# EStop.net
KiCad netlist of a schematic drawn in Altium Designer
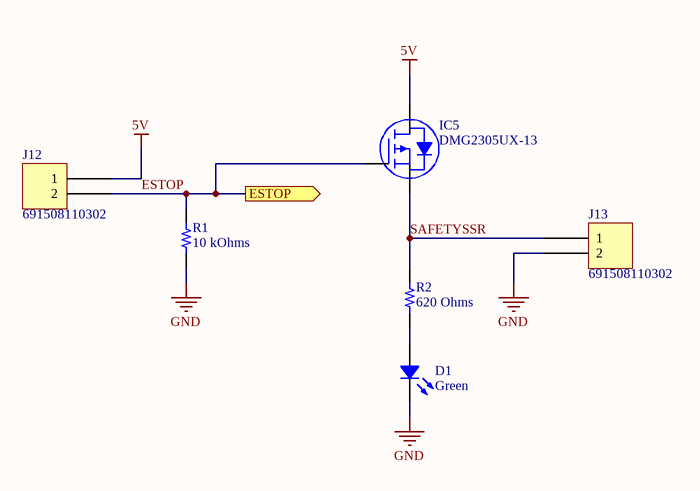
[diagram p0: EStop.SchDoc]

(export (version "E")
  (design (tool "Eeschema 10.0.6"))
  (components
    (comp (ref "D1")
      (value "Green")
      (footprint "LED 0603_1608 GREEN")
      (description "LED GREEN CLEAR CHIP SMD")
      (fields (field (name "PART NUMBER") "LTST-C190KGKT") (field (name "MANUFACTURER") "Lite-On Inc."))
      (libsource (lib "Celestial Altium Library - altium_library") (part "LED"))
    )
    (comp (ref "IC5")
      (value "DMG2305UX-13")
      (footprint "DIODES SOT-23-3")
      (description "MOSFET P-CH 20V 4.2A SOT23")
      (fields (field (name "MANUFACTURER") "Diodes Incorporated"))
      (libsource (lib "Celestial Altium Library - altium_library") (part "DIODES MOSFET P-CH SOT-23-3"))
    )
    (comp (ref "J12")
      (value "691508110302")
      (footprint "WURTH 691508110302")
      (description "TERM BLOCK 2POS 3.5MM SMD")
      (fields (field (name "MANUFACTURER") "Würth Elektronik") (field (name "VOLTAGE") "300V"))
      (libsource (lib "Celestial Altium Library - altium_library") (part "2 Pin"))
    )
    (comp (ref "J13")
      (value "691508110302")
      (footprint "WURTH 691508110302")
      (description "TERM BLOCK 2POS 3.5MM SMD")
      (fields (field (name "MANUFACTURER") "Würth Elektronik") (field (name "VOLTAGE") "300V"))
      (libsource (lib "") (part "2 Pin_1"))
    )
    (comp (ref "R1")
      (value "10 kOhms")
      (footprint "RES 0603_1608")
      (description "RES SMD 10K OHM 5% 1/4W 0603")
      (fields
        (field (name "PART NUMBER") "ERJ-PA3J103V")
        (field (name "MANUFACTURER") "Panasonic Electronic Components")
      )
      (libsource (lib "Celestial Altium Library - altium_library") (part "Resistor"))
    )
    (comp (ref "R2")
      (value "620 Ohms")
      (footprint "RES 0603_1608")
      (description "RES SMD 620 OHM 5% 1/10W 0603")
      (fields
        (field (name "PART NUMBER") "ERJ-3GEYJ621V")
        (field (name "MANUFACTURER") "Panasonic Electronic Components")
      )
      (libsource (lib "Celestial Altium Library - altium_library") (part "Resistor"))
    )
  )
  (nets
    (net (code "1") (name "/ESTOP") (class "Default")
      (node (ref "IC5") (pin "1") (pinfunction "G_1") (pintype "passive"))
      (node (ref "J12") (pin "2") (pinfunction "2_2") (pintype "passive"))
      (node (ref "R1") (pin "2") (pinfunction "2_2") (pintype "passive"))
    )
    (net (code "2") (name "/SAFETYSSR") (class "Default")
      (node (ref "IC5") (pin "2") (pinfunction "S_2") (pintype "passive"))
      (node (ref "J13") (pin "1") (pinfunction "1_1") (pintype "passive"))
      (node (ref "R2") (pin "2") (pinfunction "2_2") (pintype "passive"))
    )
    (net (code "3") (name "5V") (class "Default")
      (node (ref "IC5") (pin "3") (pinfunction "D_3") (pintype "passive"))
      (node (ref "J12") (pin "1") (pinfunction "1_1") (pintype "passive"))
    )
    (net (code "4") (name "GND") (class "Default")
      (node (ref "D1") (pin "2") (pinfunction "2_2") (pintype "passive"))
      (node (ref "J13") (pin "2") (pinfunction "2_2") (pintype "passive"))
      (node (ref "R1") (pin "1") (pinfunction "1_1") (pintype "passive"))
    )
    (net (code "5") (name "Net-(D1-Pad1)") (class "Default")
      (node (ref "D1") (pin "1") (pinfunction "1_1") (pintype "passive"))
      (node (ref "R2") (pin "1") (pinfunction "1_1") (pintype "passive"))
    )
  )
)
